# sqore.net
KiCad netlist of a schematic drawn in EAGLE
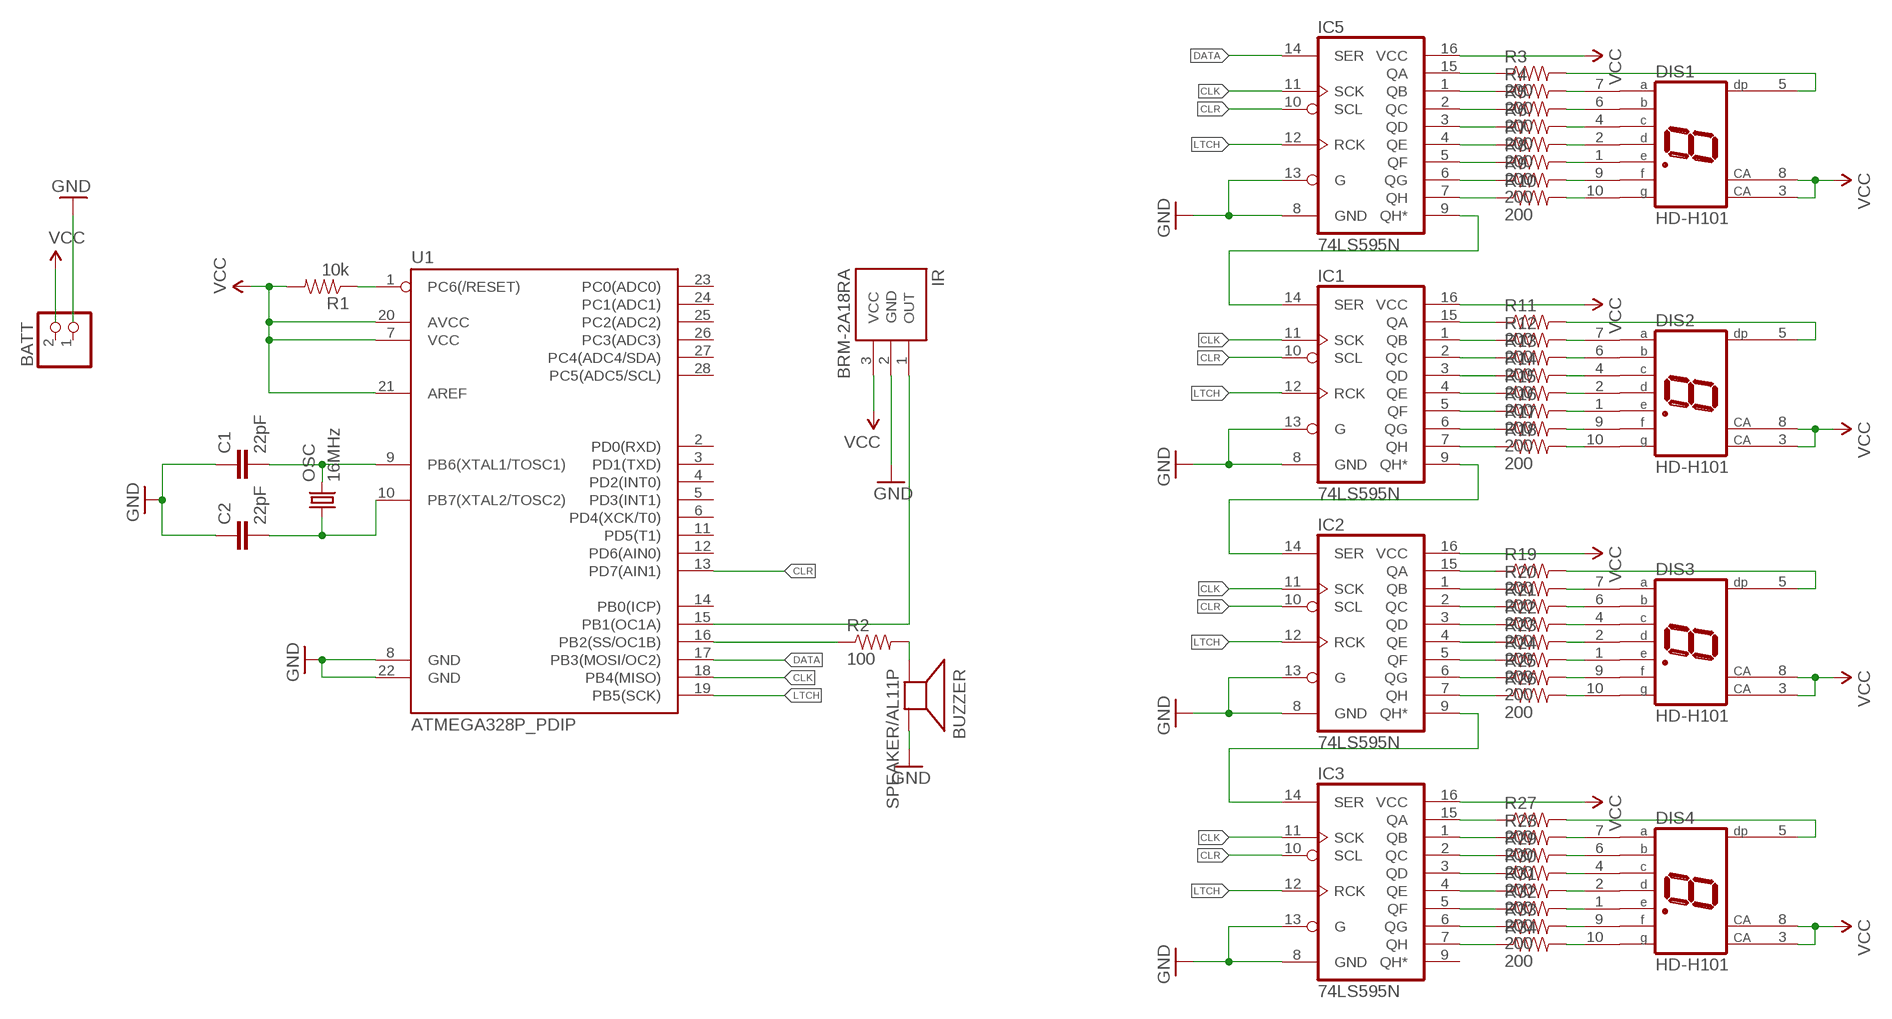
[diagram p0: schematic, sheet 1]

(export (version "E")
  (design (tool "Eeschema 10.0.6"))
  (components
    (comp (ref "BATT")
      (value "JST_2PIN-THM")
      (footprint "eagle-import:JST-PH-2-THM")
      (libsource (lib "eagle-import") (part "JST_2PIN-THM"))
    )
    (comp (ref "BUZZER")
      (value "SPEAKER/AL11P")
      (footprint "eagle-import:AL11P")
      (libsource (lib "eagle-import") (part "SPEAKER/AL11P"))
    )
    (comp (ref "C1")
      (value "22pF")
      (footprint "eagle-import:CAP-PTH-SMALL-KIT")
      (libsource (lib "eagle-import") (part "CAPKIT"))
    )
    (comp (ref "C2")
      (value "22pF")
      (footprint "eagle-import:CAP-PTH-SMALL-KIT")
      (libsource (lib "eagle-import") (part "CAPKIT"))
    )
    (comp (ref "DIS1")
      (value "HD-H101")
      (footprint "eagle-import:HDSP-M")
      (libsource (lib "eagle-import") (part "HD-H101"))
    )
    (comp (ref "DIS2")
      (value "HD-H101")
      (footprint "eagle-import:HDSP-M")
      (libsource (lib "eagle-import") (part "HD-H101"))
    )
    (comp (ref "DIS3")
      (value "HD-H101")
      (footprint "eagle-import:HDSP-M")
      (libsource (lib "eagle-import") (part "HD-H101"))
    )
    (comp (ref "DIS4")
      (value "HD-H101")
      (footprint "eagle-import:HDSP-M")
      (libsource (lib "eagle-import") (part "HD-H101"))
    )
    (comp (ref "IC1")
      (value "74LS595N")
      (footprint "eagle-import:DIL16")
      (libsource (lib "eagle-import") (part "74595NLS"))
    )
    (comp (ref "IC2")
      (value "74LS595N")
      (footprint "eagle-import:DIL16")
      (libsource (lib "eagle-import") (part "74595NLS"))
    )
    (comp (ref "IC3")
      (value "74LS595N")
      (footprint "eagle-import:DIL16")
      (libsource (lib "eagle-import") (part "74595NLS"))
    )
    (comp (ref "IC5")
      (value "74LS595N")
      (footprint "eagle-import:DIL16")
      (libsource (lib "eagle-import") (part "74595NLS"))
    )
    (comp (ref "IR")
      (value "BRM-2A18RA")
      (footprint "eagle-import:BRM-2508")
      (libsource (lib "eagle-import") (part "BRM-2A18RA"))
    )
    (comp (ref "OSC")
      (value "16MHz")
      (footprint "eagle-import:HC49US")
      (libsource (lib "eagle-import") (part "CRYSTALHC49US"))
    )
    (comp (ref "R1")
      (value "10k")
      (footprint "eagle-import:AXIAL-0.3-KIT")
      (libsource (lib "eagle-import") (part "RESISTORKIT"))
    )
    (comp (ref "R2")
      (value "100")
      (footprint "eagle-import:AXIAL-0.3-KIT")
      (libsource (lib "eagle-import") (part "RESISTORKIT"))
    )
    (comp (ref "R3")
      (value "200")
      (footprint "eagle-import:AXIAL-0.3-KIT")
      (libsource (lib "eagle-import") (part "RESISTORKIT"))
    )
    (comp (ref "R4")
      (value "200")
      (footprint "eagle-import:AXIAL-0.3-KIT")
      (libsource (lib "eagle-import") (part "RESISTORKIT"))
    )
    (comp (ref "R5")
      (value "200")
      (footprint "eagle-import:AXIAL-0.3-KIT")
      (libsource (lib "eagle-import") (part "RESISTORKIT"))
    )
    (comp (ref "R6")
      (value "200")
      (footprint "eagle-import:AXIAL-0.3-KIT")
      (libsource (lib "eagle-import") (part "RESISTORKIT"))
    )
    (comp (ref "R7")
      (value "200")
      (footprint "eagle-import:AXIAL-0.3-KIT")
      (libsource (lib "eagle-import") (part "RESISTORKIT"))
    )
    (comp (ref "R8")
      (value "200")
      (footprint "eagle-import:AXIAL-0.3-KIT")
      (libsource (lib "eagle-import") (part "RESISTORKIT"))
    )
    (comp (ref "R9")
      (value "200")
      (footprint "eagle-import:AXIAL-0.3-KIT")
      (libsource (lib "eagle-import") (part "RESISTORKIT"))
    )
    (comp (ref "R10")
      (value "200")
      (footprint "eagle-import:AXIAL-0.3-KIT")
      (libsource (lib "eagle-import") (part "RESISTORKIT"))
    )
    (comp (ref "R11")
      (value "200")
      (footprint "eagle-import:AXIAL-0.3-KIT")
      (libsource (lib "eagle-import") (part "RESISTORKIT"))
    )
    (comp (ref "R12")
      (value "200")
      (footprint "eagle-import:AXIAL-0.3-KIT")
      (libsource (lib "eagle-import") (part "RESISTORKIT"))
    )
    (comp (ref "R13")
      (value "200")
      (footprint "eagle-import:AXIAL-0.3-KIT")
      (libsource (lib "eagle-import") (part "RESISTORKIT"))
    )
    (comp (ref "R14")
      (value "200")
      (footprint "eagle-import:AXIAL-0.3-KIT")
      (libsource (lib "eagle-import") (part "RESISTORKIT"))
    )
    (comp (ref "R15")
      (value "200")
      (footprint "eagle-import:AXIAL-0.3-KIT")
      (libsource (lib "eagle-import") (part "RESISTORKIT"))
    )
    (comp (ref "R16")
      (value "200")
      (footprint "eagle-import:AXIAL-0.3-KIT")
      (libsource (lib "eagle-import") (part "RESISTORKIT"))
    )
    (comp (ref "R17")
      (value "200")
      (footprint "eagle-import:AXIAL-0.3-KIT")
      (libsource (lib "eagle-import") (part "RESISTORKIT"))
    )
    (comp (ref "R18")
      (value "200")
      (footprint "eagle-import:AXIAL-0.3-KIT")
      (libsource (lib "eagle-import") (part "RESISTORKIT"))
    )
    (comp (ref "R19")
      (value "200")
      (footprint "eagle-import:AXIAL-0.3-KIT")
      (libsource (lib "eagle-import") (part "RESISTORKIT"))
    )
    (comp (ref "R20")
      (value "200")
      (footprint "eagle-import:AXIAL-0.3-KIT")
      (libsource (lib "eagle-import") (part "RESISTORKIT"))
    )
    (comp (ref "R21")
      (value "200")
      (footprint "eagle-import:AXIAL-0.3-KIT")
      (libsource (lib "eagle-import") (part "RESISTORKIT"))
    )
    (comp (ref "R22")
      (value "200")
      (footprint "eagle-import:AXIAL-0.3-KIT")
      (libsource (lib "eagle-import") (part "RESISTORKIT"))
    )
    (comp (ref "R23")
      (value "200")
      (footprint "eagle-import:AXIAL-0.3-KIT")
      (libsource (lib "eagle-import") (part "RESISTORKIT"))
    )
    (comp (ref "R24")
      (value "200")
      (footprint "eagle-import:AXIAL-0.3-KIT")
      (libsource (lib "eagle-import") (part "RESISTORKIT"))
    )
    (comp (ref "R25")
      (value "200")
      (footprint "eagle-import:AXIAL-0.3-KIT")
      (libsource (lib "eagle-import") (part "RESISTORKIT"))
    )
    (comp (ref "R26")
      (value "200")
      (footprint "eagle-import:AXIAL-0.3-KIT")
      (libsource (lib "eagle-import") (part "RESISTORKIT"))
    )
    (comp (ref "R27")
      (value "200")
      (footprint "eagle-import:AXIAL-0.3-KIT")
      (libsource (lib "eagle-import") (part "RESISTORKIT"))
    )
    (comp (ref "R28")
      (value "200")
      (footprint "eagle-import:AXIAL-0.3-KIT")
      (libsource (lib "eagle-import") (part "RESISTORKIT"))
    )
    (comp (ref "R29")
      (value "200")
      (footprint "eagle-import:AXIAL-0.3-KIT")
      (libsource (lib "eagle-import") (part "RESISTORKIT"))
    )
    (comp (ref "R30")
      (value "200")
      (footprint "eagle-import:AXIAL-0.3-KIT")
      (libsource (lib "eagle-import") (part "RESISTORKIT"))
    )
    (comp (ref "R31")
      (value "200")
      (footprint "eagle-import:AXIAL-0.3-KIT")
      (libsource (lib "eagle-import") (part "RESISTORKIT"))
    )
    (comp (ref "R32")
      (value "200")
      (footprint "eagle-import:AXIAL-0.3-KIT")
      (libsource (lib "eagle-import") (part "RESISTORKIT"))
    )
    (comp (ref "R33")
      (value "200")
      (footprint "eagle-import:AXIAL-0.3-KIT")
      (libsource (lib "eagle-import") (part "RESISTORKIT"))
    )
    (comp (ref "R34")
      (value "200")
      (footprint "eagle-import:AXIAL-0.3-KIT")
      (libsource (lib "eagle-import") (part "RESISTORKIT"))
    )
    (comp (ref "U1")
      (value "ATMEGA328P_PDIP")
      (footprint "eagle-import:DIL28-3")
      (libsource (lib "eagle-import") (part "ATMEGA328P_PDIP"))
    )
  )
  (nets
    (net (code "1") (name "CLK") (class "Default")
      (node (ref "IC1") (pin "11") (pinfunction "SCK_11") (pintype "input"))
      (node (ref "IC2") (pin "11") (pinfunction "SCK_11") (pintype "input"))
      (node (ref "IC3") (pin "11") (pinfunction "SCK_11") (pintype "input"))
      (node (ref "IC5") (pin "11") (pinfunction "SCK_11") (pintype "input"))
      (node (ref "U1") (pin "18") (pinfunction "PB4(MISO)_18") (pintype "bidirectional"))
    )
    (net (code "2") (name "CLR") (class "Default")
      (node (ref "IC1") (pin "10") (pinfunction "SCL_10") (pintype "input"))
      (node (ref "IC2") (pin "10") (pinfunction "SCL_10") (pintype "input"))
      (node (ref "IC3") (pin "10") (pinfunction "SCL_10") (pintype "input"))
      (node (ref "IC5") (pin "10") (pinfunction "SCL_10") (pintype "input"))
      (node (ref "U1") (pin "13") (pinfunction "PD7(AIN1)_13") (pintype "bidirectional"))
    )
    (net (code "3") (name "DATA") (class "Default")
      (node (ref "IC5") (pin "14") (pinfunction "SER_14") (pintype "input"))
      (node (ref "U1") (pin "17") (pinfunction "PB3(MOSI/OC2)_17") (pintype "bidirectional"))
    )
    (net (code "4") (name "GND") (class "Default")
      (node (ref "BUZZER") (pin "-") (pinfunction "-_-") (pintype "passive"))
      (node (ref "C1") (pin "1") (pinfunction "1_1") (pintype "passive"))
      (node (ref "C2") (pin "1") (pinfunction "1_1") (pintype "passive"))
      (node (ref "IC1") (pin "13") (pinfunction "G_13") (pintype "input"))
      (node (ref "IC1") (pin "8") (pinfunction "GND_8") (pintype "power_in"))
      (node (ref "IC2") (pin "13") (pinfunction "G_13") (pintype "input"))
      (node (ref "IC2") (pin "8") (pinfunction "GND_8") (pintype "power_in"))
      (node (ref "IC3") (pin "13") (pinfunction "G_13") (pintype "input"))
      (node (ref "IC3") (pin "8") (pinfunction "GND_8") (pintype "power_in"))
      (node (ref "IC5") (pin "13") (pinfunction "G_13") (pintype "input"))
      (node (ref "IC5") (pin "8") (pinfunction "GND_8") (pintype "power_in"))
      (node (ref "IR") (pin "2") (pinfunction "GND_2") (pintype "bidirectional"))
      (node (ref "U1") (pin "22") (pinfunction "GND_22") (pintype "bidirectional"))
      (node (ref "U1") (pin "8") (pinfunction "GND_8") (pintype "bidirectional"))
    )
    (net (code "5") (name "LTCH") (class "Default")
      (node (ref "IC1") (pin "12") (pinfunction "RCK_12") (pintype "input"))
      (node (ref "IC2") (pin "12") (pinfunction "RCK_12") (pintype "input"))
      (node (ref "IC3") (pin "12") (pinfunction "RCK_12") (pintype "input"))
      (node (ref "IC5") (pin "12") (pinfunction "RCK_12") (pintype "input"))
      (node (ref "U1") (pin "19") (pinfunction "PB5(SCK)_19") (pintype "bidirectional"))
    )
    (net (code "6") (name "Net-(DIS1-A)") (class "Default")
      (node (ref "DIS1") (pin "7") (pinfunction "A_7") (pintype "passive"))
      (node (ref "R4") (pin "P$2") (pinfunction "2_P$2") (pintype "passive"))
    )
    (net (code "7") (name "Net-(DIS1-B)") (class "Default")
      (node (ref "DIS1") (pin "6") (pinfunction "B_6") (pintype "passive"))
      (node (ref "R5") (pin "P$2") (pinfunction "2_P$2") (pintype "passive"))
    )
    (net (code "8") (name "Net-(DIS1-C)") (class "Default")
      (node (ref "DIS1") (pin "4") (pinfunction "C_4") (pintype "passive"))
      (node (ref "R6") (pin "P$2") (pinfunction "2_P$2") (pintype "passive"))
    )
    (net (code "9") (name "Net-(DIS1-D)") (class "Default")
      (node (ref "DIS1") (pin "2") (pinfunction "D_2") (pintype "passive"))
      (node (ref "R7") (pin "P$2") (pinfunction "2_P$2") (pintype "passive"))
    )
    (net (code "10") (name "Net-(DIS1-DP)") (class "Default")
      (node (ref "DIS1") (pin "5") (pinfunction "DP_5") (pintype "passive"))
      (node (ref "R3") (pin "P$2") (pinfunction "2_P$2") (pintype "passive"))
    )
    (net (code "11") (name "Net-(DIS1-E)") (class "Default")
      (node (ref "DIS1") (pin "1") (pinfunction "E_1") (pintype "passive"))
      (node (ref "R8") (pin "P$2") (pinfunction "2_P$2") (pintype "passive"))
    )
    (net (code "12") (name "Net-(DIS1-F)") (class "Default")
      (node (ref "DIS1") (pin "9") (pinfunction "F_9") (pintype "passive"))
      (node (ref "R9") (pin "P$2") (pinfunction "2_P$2") (pintype "passive"))
    )
    (net (code "13") (name "Net-(DIS1-G)") (class "Default")
      (node (ref "DIS1") (pin "10") (pinfunction "G_10") (pintype "passive"))
      (node (ref "R10") (pin "P$2") (pinfunction "2_P$2") (pintype "passive"))
    )
    (net (code "14") (name "Net-(DIS2-A)") (class "Default")
      (node (ref "DIS2") (pin "7") (pinfunction "A_7") (pintype "passive"))
      (node (ref "R12") (pin "P$2") (pinfunction "2_P$2") (pintype "passive"))
    )
    (net (code "15") (name "Net-(DIS2-B)") (class "Default")
      (node (ref "DIS2") (pin "6") (pinfunction "B_6") (pintype "passive"))
      (node (ref "R13") (pin "P$2") (pinfunction "2_P$2") (pintype "passive"))
    )
    (net (code "16") (name "Net-(DIS2-C)") (class "Default")
      (node (ref "DIS2") (pin "4") (pinfunction "C_4") (pintype "passive"))
      (node (ref "R14") (pin "P$2") (pinfunction "2_P$2") (pintype "passive"))
    )
    (net (code "17") (name "Net-(DIS2-D)") (class "Default")
      (node (ref "DIS2") (pin "2") (pinfunction "D_2") (pintype "passive"))
      (node (ref "R15") (pin "P$2") (pinfunction "2_P$2") (pintype "passive"))
    )
    (net (code "18") (name "Net-(DIS2-DP)") (class "Default")
      (node (ref "DIS2") (pin "5") (pinfunction "DP_5") (pintype "passive"))
      (node (ref "R11") (pin "P$2") (pinfunction "2_P$2") (pintype "passive"))
    )
    (net (code "19") (name "Net-(DIS2-E)") (class "Default")
      (node (ref "DIS2") (pin "1") (pinfunction "E_1") (pintype "passive"))
      (node (ref "R16") (pin "P$2") (pinfunction "2_P$2") (pintype "passive"))
    )
    (net (code "20") (name "Net-(DIS2-F)") (class "Default")
      (node (ref "DIS2") (pin "9") (pinfunction "F_9") (pintype "passive"))
      (node (ref "R17") (pin "P$2") (pinfunction "2_P$2") (pintype "passive"))
    )
    (net (code "21") (name "Net-(DIS2-G)") (class "Default")
      (node (ref "DIS2") (pin "10") (pinfunction "G_10") (pintype "passive"))
      (node (ref "R18") (pin "P$2") (pinfunction "2_P$2") (pintype "passive"))
    )
    (net (code "22") (name "Net-(DIS3-A)") (class "Default")
      (node (ref "DIS3") (pin "7") (pinfunction "A_7") (pintype "passive"))
      (node (ref "R20") (pin "P$2") (pinfunction "2_P$2") (pintype "passive"))
    )
    (net (code "23") (name "Net-(DIS3-B)") (class "Default")
      (node (ref "DIS3") (pin "6") (pinfunction "B_6") (pintype "passive"))
      (node (ref "R21") (pin "P$2") (pinfunction "2_P$2") (pintype "passive"))
    )
    (net (code "24") (name "Net-(DIS3-C)") (class "Default")
      (node (ref "DIS3") (pin "4") (pinfunction "C_4") (pintype "passive"))
      (node (ref "R22") (pin "P$2") (pinfunction "2_P$2") (pintype "passive"))
    )
    (net (code "25") (name "Net-(DIS3-D)") (class "Default")
      (node (ref "DIS3") (pin "2") (pinfunction "D_2") (pintype "passive"))
      (node (ref "R23") (pin "P$2") (pinfunction "2_P$2") (pintype "passive"))
    )
    (net (code "26") (name "Net-(DIS3-DP)") (class "Default")
      (node (ref "DIS3") (pin "5") (pinfunction "DP_5") (pintype "passive"))
      (node (ref "R19") (pin "P$2") (pinfunction "2_P$2") (pintype "passive"))
    )
    (net (code "27") (name "Net-(DIS3-E)") (class "Default")
      (node (ref "DIS3") (pin "1") (pinfunction "E_1") (pintype "passive"))
      (node (ref "R24") (pin "P$2") (pinfunction "2_P$2") (pintype "passive"))
    )
    (net (code "28") (name "Net-(DIS3-F)") (class "Default")
      (node (ref "DIS3") (pin "9") (pinfunction "F_9") (pintype "passive"))
      (node (ref "R25") (pin "P$2") (pinfunction "2_P$2") (pintype "passive"))
    )
    (net (code "29") (name "Net-(DIS3-G)") (class "Default")
      (node (ref "DIS3") (pin "10") (pinfunction "G_10") (pintype "passive"))
      (node (ref "R26") (pin "P$2") (pinfunction "2_P$2") (pintype "passive"))
    )
    (net (code "30") (name "Net-(DIS4-A)") (class "Default")
      (node (ref "DIS4") (pin "7") (pinfunction "A_7") (pintype "passive"))
      (node (ref "R28") (pin "P$2") (pinfunction "2_P$2") (pintype "passive"))
    )
    (net (code "31") (name "Net-(DIS4-B)") (class "Default")
      (node (ref "DIS4") (pin "6") (pinfunction "B_6") (pintype "passive"))
      (node (ref "R29") (pin "P$2") (pinfunction "2_P$2") (pintype "passive"))
    )
    (net (code "32") (name "Net-(DIS4-C)") (class "Default")
      (node (ref "DIS4") (pin "4") (pinfunction "C_4") (pintype "passive"))
      (node (ref "R30") (pin "P$2") (pinfunction "2_P$2") (pintype "passive"))
    )
    (net (code "33") (name "Net-(DIS4-D)") (class "Default")
      (node (ref "DIS4") (pin "2") (pinfunction "D_2") (pintype "passive"))
      (node (ref "R31") (pin "P$2") (pinfunction "2_P$2") (pintype "passive"))
    )
    (net (code "34") (name "Net-(DIS4-DP)") (class "Default")
      (node (ref "DIS4") (pin "5") (pinfunction "DP_5") (pintype "passive"))
      (node (ref "R27") (pin "P$2") (pinfunction "2_P$2") (pintype "passive"))
    )
    (net (code "35") (name "Net-(DIS4-E)") (class "Default")
      (node (ref "DIS4") (pin "1") (pinfunction "E_1") (pintype "passive"))
      (node (ref "R32") (pin "P$2") (pinfunction "2_P$2") (pintype "passive"))
    )
    (net (code "36") (name "Net-(DIS4-F)") (class "Default")
      (node (ref "DIS4") (pin "9") (pinfunction "F_9") (pintype "passive"))
      (node (ref "R33") (pin "P$2") (pinfunction "2_P$2") (pintype "passive"))
    )
    (net (code "37") (name "Net-(DIS4-G)") (class "Default")
      (node (ref "DIS4") (pin "10") (pinfunction "G_10") (pintype "passive"))
      (node (ref "R34") (pin "P$2") (pinfunction "2_P$2") (pintype "passive"))
    )
    (net (code "38") (name "Net-(IC1-QA)") (class "Default")
      (node (ref "IC1") (pin "15") (pinfunction "QA_15") (pintype "tri_state"))
      (node (ref "R11") (pin "P$1") (pinfunction "1_P$1") (pintype "passive"))
    )
    (net (code "39") (name "Net-(IC1-QB)") (class "Default")
      (node (ref "IC1") (pin "1") (pinfunction "QB_1") (pintype "tri_state"))
      (node (ref "R12") (pin "P$1") (pinfunction "1_P$1") (pintype "passive"))
    )
    (net (code "40") (name "Net-(IC1-QC)") (class "Default")
      (node (ref "IC1") (pin "2") (pinfunction "QC_2") (pintype "tri_state"))
      (node (ref "R13") (pin "P$1") (pinfunction "1_P$1") (pintype "passive"))
    )
    (net (code "41") (name "Net-(IC1-QD)") (class "Default")
      (node (ref "IC1") (pin "3") (pinfunction "QD_3") (pintype "tri_state"))
      (node (ref "R14") (pin "P$1") (pinfunction "1_P$1") (pintype "passive"))
    )
    (net (code "42") (name "Net-(IC1-QE)") (class "Default")
      (node (ref "IC1") (pin "4") (pinfunction "QE_4") (pintype "tri_state"))
      (node (ref "R15") (pin "P$1") (pinfunction "1_P$1") (pintype "passive"))
    )
    (net (code "43") (name "Net-(IC1-QF)") (class "Default")
      (node (ref "IC1") (pin "5") (pinfunction "QF_5") (pintype "tri_state"))
      (node (ref "R16") (pin "P$1") (pinfunction "1_P$1") (pintype "passive"))
    )
    (net (code "44") (name "Net-(IC1-QG)") (class "Default")
      (node (ref "IC1") (pin "6") (pinfunction "QG_6") (pintype "tri_state"))
      (node (ref "R17") (pin "P$1") (pinfunction "1_P$1") (pintype "passive"))
    )
    (net (code "45") (name "Net-(IC1-QH)") (class "Default")
      (node (ref "IC1") (pin "7") (pinfunction "QH_7") (pintype "tri_state"))
      (node (ref "R18") (pin "P$1") (pinfunction "1_P$1") (pintype "passive"))
    )
    (net (code "46") (name "Net-(IC1-QH*)") (class "Default")
      (node (ref "IC1") (pin "9") (pinfunction "QH*_9") (pintype "tri_state"))
      (node (ref "IC2") (pin "14") (pinfunction "SER_14") (pintype "input"))
    )
    (net (code "47") (name "Net-(IC1-SER)") (class "Default")
      (node (ref "IC1") (pin "14") (pinfunction "SER_14") (pintype "input"))
      (node (ref "IC5") (pin "9") (pinfunction "QH*_9") (pintype "tri_state"))
    )
    (net (code "48") (name "Net-(IC2-QA)") (class "Default")
      (node (ref "IC2") (pin "15") (pinfunction "QA_15") (pintype "tri_state"))
      (node (ref "R19") (pin "P$1") (pinfunction "1_P$1") (pintype "passive"))
    )
    (net (code "49") (name "Net-(IC2-QB)") (class "Default")
      (node (ref "IC2") (pin "1") (pinfunction "QB_1") (pintype "tri_state"))
      (node (ref "R20") (pin "P$1") (pinfunction "1_P$1") (pintype "passive"))
    )
    (net (code "50") (name "Net-(IC2-QC)") (class "Default")
      (node (ref "IC2") (pin "2") (pinfunction "QC_2") (pintype "tri_state"))
      (node (ref "R21") (pin "P$1") (pinfunction "1_P$1") (pintype "passive"))
    )
    (net (code "51") (name "Net-(IC2-QD)") (class "Default")
      (node (ref "IC2") (pin "3") (pinfunction "QD_3") (pintype "tri_state"))
      (node (ref "R22") (pin "P$1") (pinfunction "1_P$1") (pintype "passive"))
    )
    (net (code "52") (name "Net-(IC2-QE)") (class "Default")
      (node (ref "IC2") (pin "4") (pinfunction "QE_4") (pintype "tri_state"))
      (node (ref "R23") (pin "P$1") (pinfunction "1_P$1") (pintype "passive"))
    )
    (net (code "53") (name "Net-(IC2-QF)") (class "Default")
      (node (ref "IC2") (pin "5") (pinfunction "QF_5") (pintype "tri_state"))
      (node (ref "R24") (pin "P$1") (pinfunction "1_P$1") (pintype "passive"))
    )
    (net (code "54") (name "Net-(IC2-QG)") (class "Default")
      (node (ref "IC2") (pin "6") (pinfunction "QG_6") (pintype "tri_state"))
      (node (ref "R25") (pin "P$1") (pinfunction "1_P$1") (pintype "passive"))
    )
    (net (code "55") (name "Net-(IC2-QH)") (class "Default")
      (node (ref "IC2") (pin "7") (pinfunction "QH_7") (pintype "tri_state"))
      (node (ref "R26") (pin "P$1") (pinfunction "1_P$1") (pintype "passive"))
    )
    (net (code "56") (name "Net-(IC2-QH*)") (class "Default")
      (node (ref "IC2") (pin "9") (pinfunction "QH*_9") (pintype "tri_state"))
      (node (ref "IC3") (pin "14") (pinfunction "SER_14") (pintype "input"))
    )
    (net (code "57") (name "Net-(IC3-QA)") (class "Default")
      (node (ref "IC3") (pin "15") (pinfunction "QA_15") (pintype "tri_state"))
      (node (ref "R27") (pin "P$1") (pinfunction "1_P$1") (pintype "passive"))
    )
    (net (code "58") (name "Net-(IC3-QB)") (class "Default")
      (node (ref "IC3") (pin "1") (pinfunction "QB_1") (pintype "tri_state"))
      (node (ref "R28") (pin "P$1") (pinfunction "1_P$1") (pintype "passive"))
    )
    (net (code "59") (name "Net-(IC3-QC)") (class "Default")
      (node (ref "IC3") (pin "2") (pinfunction "QC_2") (pintype "tri_state"))
      (node (ref "R29") (pin "P$1") (pinfunction "1_P$1") (pintype "passive"))
    )
    (net (code "60") (name "Net-(IC3-QD)") (class "Default")
      (node (ref "IC3") (pin "3") (pinfunction "QD_3") (pintype "tri_state"))
      (node (ref "R30") (pin "P$1") (pinfunction "1_P$1") (pintype "passive"))
    )
    (net (code "61") (name "Net-(IC3-QE)") (class "Default")
      (node (ref "IC3") (pin "4") (pinfunction "QE_4") (pintype "tri_state"))
      (node (ref "R31") (pin "P$1") (pinfunction "1_P$1") (pintype "passive"))
    )
    (net (code "62") (name "Net-(IC3-QF)") (class "Default")
      (node (ref "IC3") (pin "5") (pinfunction "QF_5") (pintype "tri_state"))
      (node (ref "R32") (pin "P$1") (pinfunction "1_P$1") (pintype "passive"))
    )
    (net (code "63") (name "Net-(IC3-QG)") (class "Default")
      (node (ref "IC3") (pin "6") (pinfunction "QG_6") (pintype "tri_state"))
      (node (ref "R33") (pin "P$1") (pinfunction "1_P$1") (pintype "passive"))
    )
    (net (code "64") (name "Net-(IC3-QH)") (class "Default")
      (node (ref "IC3") (pin "7") (pinfunction "QH_7") (pintype "tri_state"))
      (node (ref "R34") (pin "P$1") (pinfunction "1_P$1") (pintype "passive"))
    )
    (net (code "65") (name "Net-(IC5-QA)") (class "Default")
      (node (ref "IC5") (pin "15") (pinfunction "QA_15") (pintype "tri_state"))
      (node (ref "R3") (pin "P$1") (pinfunction "1_P$1") (pintype "passive"))
    )
    (net (code "66") (name "Net-(IC5-QB)") (class "Default")
      (node (ref "IC5") (pin "1") (pinfunction "QB_1") (pintype "tri_state"))
      (node (ref "R4") (pin "P$1") (pinfunction "1_P$1") (pintype "passive"))
    )
    (net (code "67") (name "Net-(IC5-QC)") (class "Default")
      (node (ref "IC5") (pin "2") (pinfunction "QC_2") (pintype "tri_state"))
      (node (ref "R5") (pin "P$1") (pinfunction "1_P$1") (pintype "passive"))
    )
    (net (code "68") (name "Net-(IC5-QD)") (class "Default")
      (node (ref "IC5") (pin "3") (pinfunction "QD_3") (pintype "tri_state"))
      (node (ref "R6") (pin "P$1") (pinfunction "1_P$1") (pintype "passive"))
    )
    (net (code "69") (name "Net-(IC5-QE)") (class "Default")
      (node (ref "IC5") (pin "4") (pinfunction "QE_4") (pintype "tri_state"))
      (node (ref "R7") (pin "P$1") (pinfunction "1_P$1") (pintype "passive"))
    )
    (net (code "70") (name "Net-(IC5-QF)") (class "Default")
      (node (ref "IC5") (pin "5") (pinfunction "QF_5") (pintype "tri_state"))
      (node (ref "R8") (pin "P$1") (pinfunction "1_P$1") (pintype "passive"))
    )
    (net (code "71") (name "Net-(IC5-QG)") (class "Default")
      (node (ref "IC5") (pin "6") (pinfunction "QG_6") (pintype "tri_state"))
      (node (ref "R9") (pin "P$1") (pinfunction "1_P$1") (pintype "passive"))
    )
    (net (code "72") (name "Net-(IC5-QH)") (class "Default")
      (node (ref "IC5") (pin "7") (pinfunction "QH_7") (pintype "tri_state"))
      (node (ref "R10") (pin "P$1") (pinfunction "1_P$1") (pintype "passive"))
    )
    (net (code "73") (name "Net-(IR-OUT)") (class "Default")
      (node (ref "IR") (pin "1") (pinfunction "OUT_1") (pintype "bidirectional"))
      (node (ref "U1") (pin "15") (pinfunction "PB1(OC1A)_15") (pintype "bidirectional"))
    )
    (net (code "74") (name "Net-(R1-1)") (class "Default")
      (node (ref "R1") (pin "P$1") (pinfunction "1_P$1") (pintype "passive"))
      (node (ref "U1") (pin "1") (pinfunction "PC6(/RESET)_1") (pintype "bidirectional"))
    )
    (net (code "75") (name "Net-(R2-1)") (class "Default")
      (node (ref "R2") (pin "P$1") (pinfunction "1_P$1") (pintype "passive"))
      (node (ref "U1") (pin "16") (pinfunction "PB2(SS/OC1B)_16") (pintype "bidirectional"))
    )
    (net (code "76") (name "Net-(R2-2)") (class "Default")
      (node (ref "BUZZER") (pin "+") (pinfunction "+_+") (pintype "passive"))
      (node (ref "R2") (pin "P$2") (pinfunction "2_P$2") (pintype "passive"))
    )
    (net (code "77") (name "Net-(U1-PB6(XTAL1{slash}TOSC1))") (class "Default")
      (node (ref "C1") (pin "2") (pinfunction "2_2") (pintype "passive"))
      (node (ref "OSC") (pin "2") (pinfunction "2_2") (pintype "passive"))
      (node (ref "U1") (pin "9") (pinfunction "PB6(XTAL1/TOSC1)_9") (pintype "bidirectional"))
    )
    (net (code "78") (name "Net-(U1-PB7(XTAL2{slash}TOSC2))") (class "Default")
      (node (ref "C2") (pin "2") (pinfunction "2_2") (pintype "passive"))
      (node (ref "OSC") (pin "1") (pinfunction "1_1") (pintype "passive"))
      (node (ref "U1") (pin "10") (pinfunction "PB7(XTAL2/TOSC2)_10") (pintype "bidirectional"))
    )
    (net (code "79") (name "VCC") (class "Default")
      (node (ref "DIS1") (pin "3") (pinfunction "CA_3") (pintype "passive"))
      (node (ref "DIS1") (pin "8") (pinfunction "CA_8") (pintype "passive"))
      (node (ref "DIS2") (pin "3") (pinfunction "CA_3") (pintype "passive"))
      (node (ref "DIS2") (pin "8") (pinfunction "CA_8") (pintype "passive"))
      (node (ref "DIS3") (pin "3") (pinfunction "CA_3") (pintype "passive"))
      (node (ref "DIS3") (pin "8") (pinfunction "CA_8") (pintype "passive"))
      (node (ref "DIS4") (pin "3") (pinfunction "CA_3") (pintype "passive"))
      (node (ref "DIS4") (pin "8") (pinfunction "CA_8") (pintype "passive"))
      (node (ref "IC1") (pin "16") (pinfunction "VCC_16") (pintype "power_in"))
      (node (ref "IC2") (pin "16") (pinfunction "VCC_16") (pintype "power_in"))
      (node (ref "IC3") (pin "16") (pinfunction "VCC_16") (pintype "power_in"))
      (node (ref "IC5") (pin "16") (pinfunction "VCC_16") (pintype "power_in"))
      (node (ref "IR") (pin "3") (pinfunction "VCC_3") (pintype "bidirectional"))
      (node (ref "R1") (pin "P$2") (pinfunction "2_P$2") (pintype "passive"))
      (node (ref "U1") (pin "20") (pinfunction "AVCC_20") (pintype "bidirectional"))
      (node (ref "U1") (pin "21") (pinfunction "AREF_21") (pintype "bidirectional"))
      (node (ref "U1") (pin "7") (pinfunction "VCC_7") (pintype "bidirectional"))
    )
    (net (code "80") (name "unconnected-(BATT-1-Pad2)") (class "Default")
      (node (ref "BATT") (pin "2") (pinfunction "1_2") (pintype "passive"))
    )
    (net (code "81") (name "unconnected-(BATT-2-Pad1)") (class "Default")
      (node (ref "BATT") (pin "1") (pinfunction "2_1") (pintype "passive"))
    )
    (net (code "82") (name "unconnected-(IC3-QH*-Pad9)") (class "Default")
      (node (ref "IC3") (pin "9") (pinfunction "QH*_9") (pintype "tri_state"))
    )
    (net (code "83") (name "unconnected-(U1-PB0(ICP)-Pad14)") (class "Default")
      (node (ref "U1") (pin "14") (pinfunction "PB0(ICP)_14") (pintype "bidirectional"))
    )
    (net (code "84") (name "unconnected-(U1-PC0(ADC0)-Pad23)") (class "Default")
      (node (ref "U1") (pin "23") (pinfunction "PC0(ADC0)_23") (pintype "bidirectional"))
    )
    (net (code "85") (name "unconnected-(U1-PC1(ADC1)-Pad24)") (class "Default")
      (node (ref "U1") (pin "24") (pinfunction "PC1(ADC1)_24") (pintype "bidirectional"))
    )
    (net (code "86") (name "unconnected-(U1-PC2(ADC2)-Pad25)") (class "Default")
      (node (ref "U1") (pin "25") (pinfunction "PC2(ADC2)_25") (pintype "bidirectional"))
    )
    (net (code "87") (name "unconnected-(U1-PC3(ADC3)-Pad26)") (class "Default")
      (node (ref "U1") (pin "26") (pinfunction "PC3(ADC3)_26") (pintype "bidirectional"))
    )
    (net (code "88") (name "unconnected-(U1-PC4(ADC4{slash}SDA)-Pad27)") (class "Default")
      (node (ref "U1") (pin "27") (pinfunction "PC4(ADC4/SDA)_27") (pintype "bidirectional"))
    )
    (net (code "89") (name "unconnected-(U1-PC5(ADC5{slash}SCL)-Pad28)") (class "Default")
      (node (ref "U1") (pin "28") (pinfunction "PC5(ADC5/SCL)_28") (pintype "bidirectional"))
    )
    (net (code "90") (name "unconnected-(U1-PD0(RXD)-Pad2)") (class "Default")
      (node (ref "U1") (pin "2") (pinfunction "PD0(RXD)_2") (pintype "bidirectional"))
    )
    (net (code "91") (name "unconnected-(U1-PD1(TXD)-Pad3)") (class "Default")
      (node (ref "U1") (pin "3") (pinfunction "PD1(TXD)_3") (pintype "bidirectional"))
    )
    (net (code "92") (name "unconnected-(U1-PD2(INT0)-Pad4)") (class "Default")
      (node (ref "U1") (pin "4") (pinfunction "PD2(INT0)_4") (pintype "bidirectional"))
    )
    (net (code "93") (name "unconnected-(U1-PD3(INT1)-Pad5)") (class "Default")
      (node (ref "U1") (pin "5") (pinfunction "PD3(INT1)_5") (pintype "bidirectional"))
    )
    (net (code "94") (name "unconnected-(U1-PD4(XCK{slash}T0)-Pad6)") (class "Default")
      (node (ref "U1") (pin "6") (pinfunction "PD4(XCK/T0)_6") (pintype "bidirectional"))
    )
    (net (code "95") (name "unconnected-(U1-PD5(T1)-Pad11)") (class "Default")
      (node (ref "U1") (pin "11") (pinfunction "PD5(T1)_11") (pintype "bidirectional"))
    )
    (net (code "96") (name "unconnected-(U1-PD6(AIN0)-Pad12)") (class "Default")
      (node (ref "U1") (pin "12") (pinfunction "PD6(AIN0)_12") (pintype "bidirectional"))
    )
  )
)
